# Final.net
KiCad netlist of a schematic drawn in EAGLE
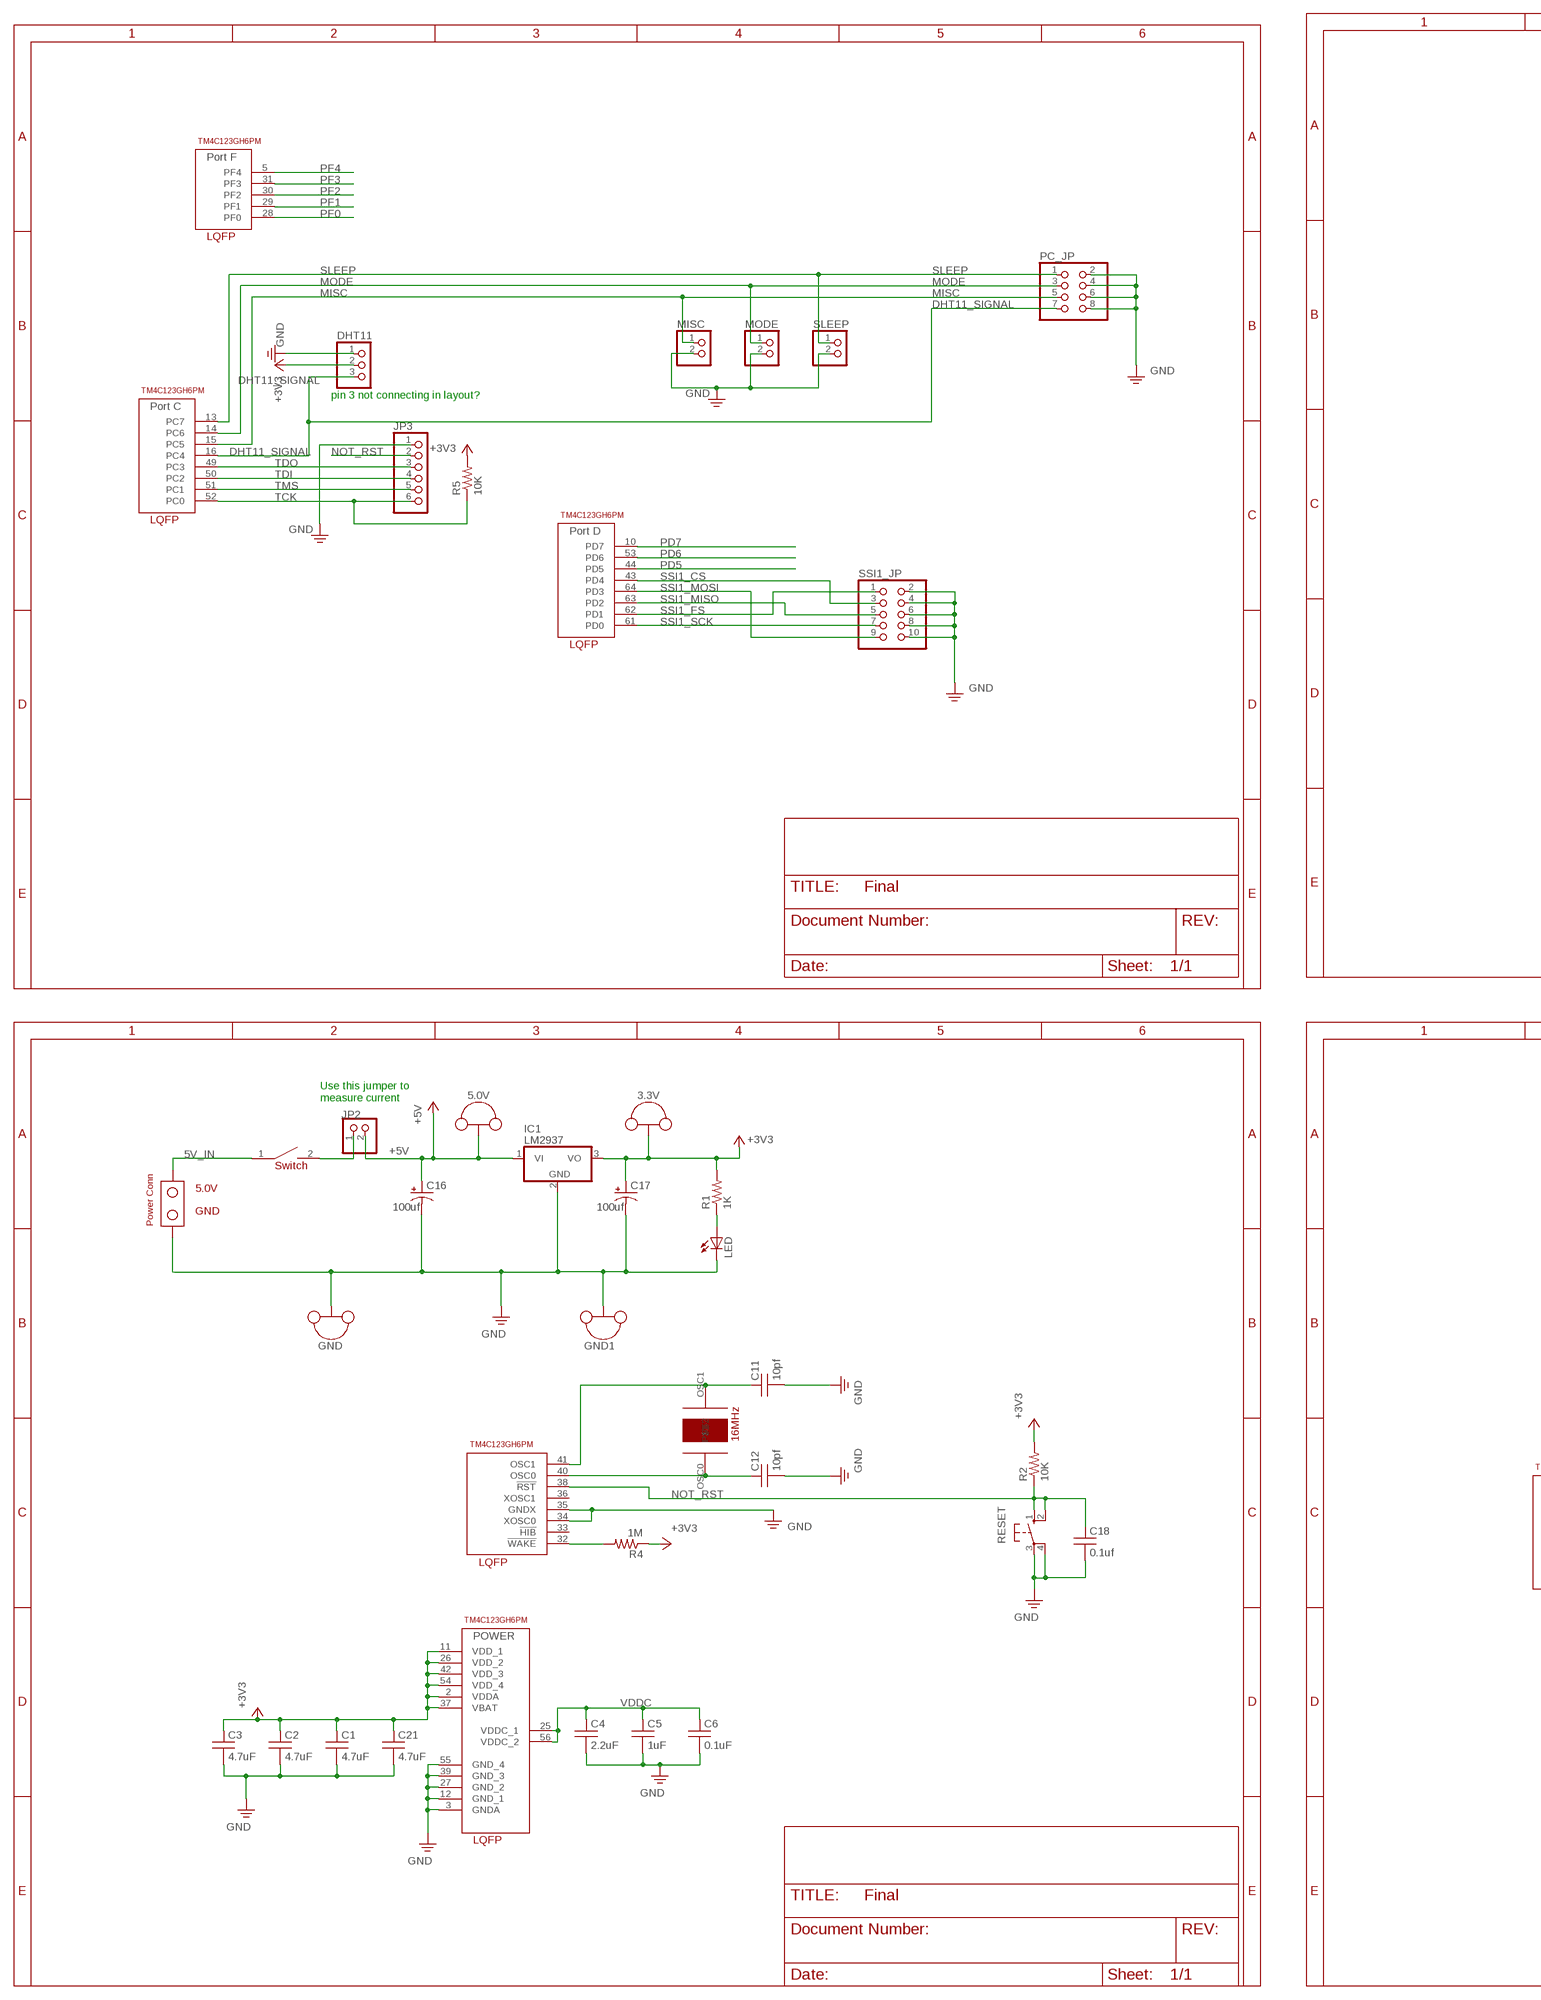
[diagram p0: schematic, sheet 1, part 1 of 2]
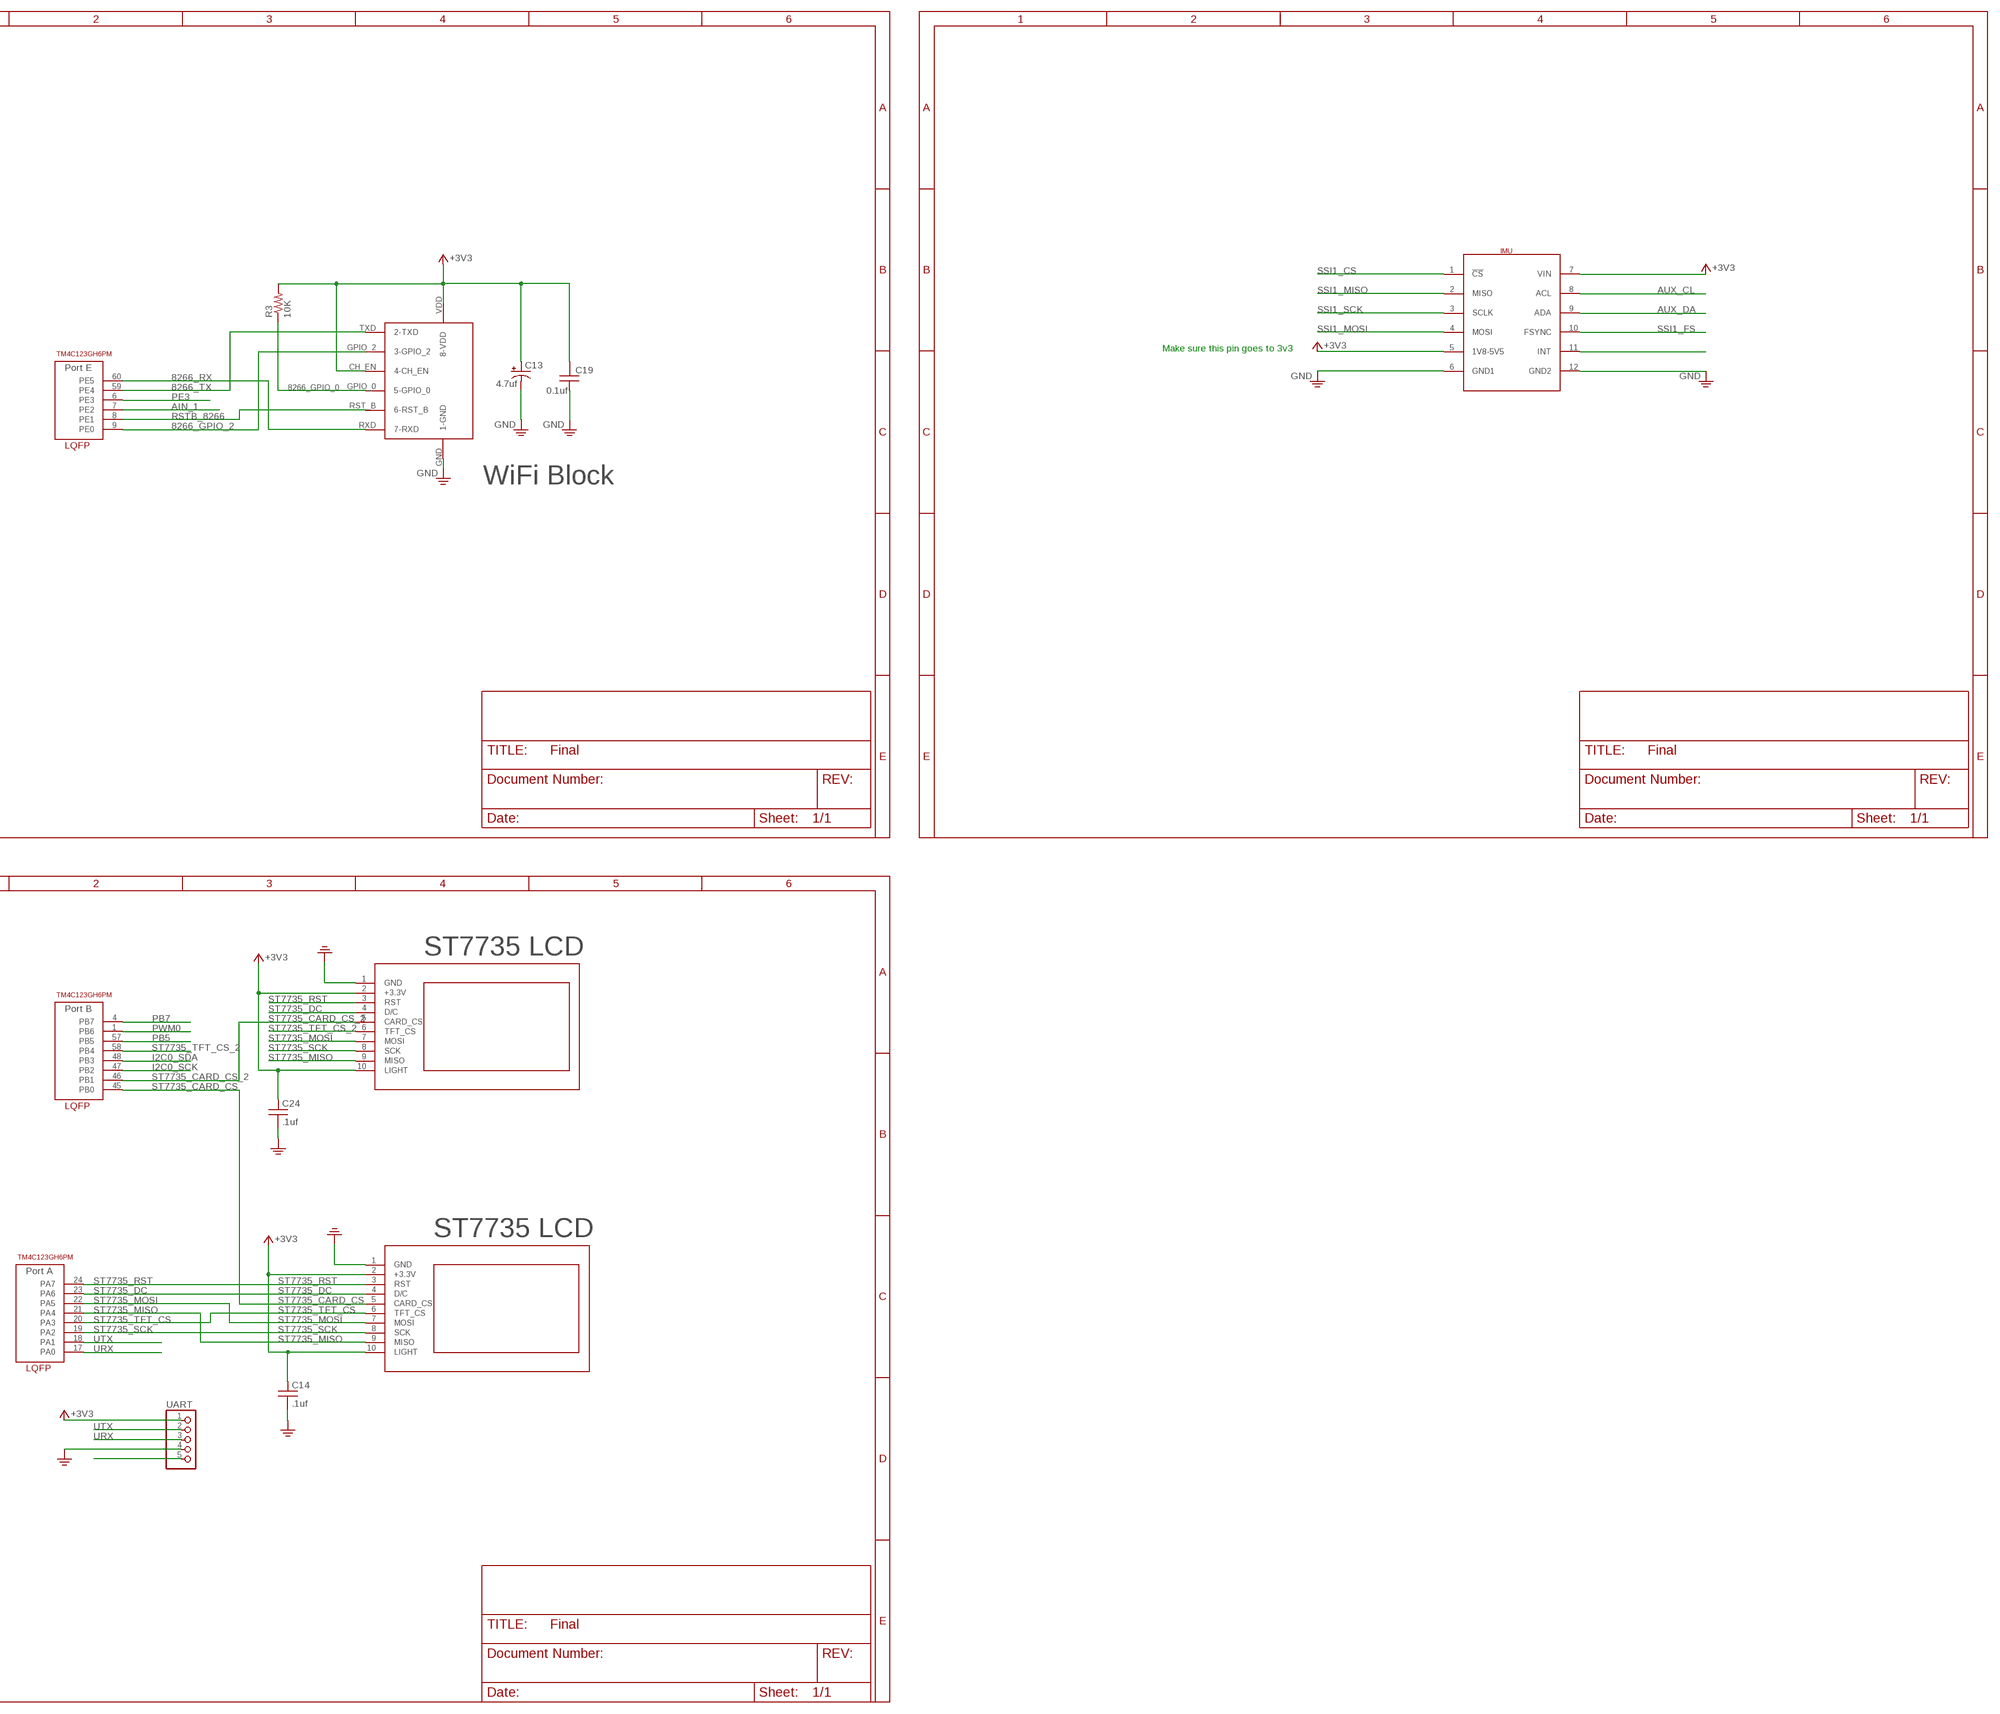
[diagram p1: schematic, sheet 1, part 2 of 2]

(export (version "E")
  (design (tool "Eeschema 10.0.6"))
  (components
    (comp (ref "3.3V")
      (value "TP_LOOP")
      (footprint "eagle-import:TP_LOOP")
      (libsource (lib "eagle-import") (part "TP_LOOP"))
    )
    (comp (ref "5.0V")
      (value "TP_LOOP")
      (footprint "eagle-import:TP_LOOP")
      (libsource (lib "eagle-import") (part "TP_LOOP"))
    )
    (comp (ref "C1")
      (value "4.7uF")
      (footprint "eagle-import:C0603K")
      (libsource (lib "eagle-import") (part "CAPACITORC0603K"))
    )
    (comp (ref "C2")
      (value "4.7uF")
      (footprint "eagle-import:C0603K")
      (libsource (lib "eagle-import") (part "CAPACITORC0603K"))
    )
    (comp (ref "C3")
      (value "4.7uF")
      (footprint "eagle-import:C0603K")
      (libsource (lib "eagle-import") (part "CAPACITORC0603K"))
    )
    (comp (ref "C4")
      (value "2.2uF")
      (footprint "eagle-import:C0603K")
      (libsource (lib "eagle-import") (part "CAPACITORC0603K"))
    )
    (comp (ref "C5")
      (value "1uF")
      (footprint "eagle-import:C0603K")
      (libsource (lib "eagle-import") (part "CAPACITORC0603K"))
    )
    (comp (ref "C6")
      (value "0.1uF")
      (footprint "eagle-import:C0603K")
      (libsource (lib "eagle-import") (part "CAPACITORC0603K"))
    )
    (comp (ref "C11")
      (value "10pf")
      (footprint "eagle-import:CAP100MIL")
      (libsource (lib "eagle-import") (part "CAPACITOR025-024X044"))
    )
    (comp (ref "C12")
      (value "10pf")
      (footprint "eagle-import:CAP100MIL")
      (libsource (lib "eagle-import") (part "CAPACITOR025-024X044"))
    )
    (comp (ref "C13")
      (value "4.7uf")
      (footprint "eagle-import:CAP200MILPOLARIZED")
      (libsource (lib "eagle-import") (part "CAPACITOR_POLARIZEDE5-6"))
    )
    (comp (ref "C14")
      (value ".1uf")
      (footprint "eagle-import:CAP200MIL")
      (libsource (lib "eagle-import") (part "CAPACITOR050-024X044"))
    )
    (comp (ref "C16")
      (value "100uf")
      (footprint "eagle-import:CAP200MILPOLARIZED")
      (libsource (lib "eagle-import") (part "CAPACITOR_POLARIZEDE5-6"))
    )
    (comp (ref "C17")
      (value "100uf")
      (footprint "eagle-import:CAP200MILPOLARIZED")
      (libsource (lib "eagle-import") (part "CAPACITOR_POLARIZEDE5-6"))
    )
    (comp (ref "C18")
      (value "0.1uf")
      (footprint "eagle-import:CAP100MIL")
      (libsource (lib "eagle-import") (part "CAPACITOR025-024X044"))
    )
    (comp (ref "C19")
      (value "0.1uf")
      (footprint "eagle-import:CAP200MIL")
      (libsource (lib "eagle-import") (part "CAPACITOR050-024X044"))
    )
    (comp (ref "C21")
      (value "4.7uF")
      (footprint "eagle-import:C0603K")
      (libsource (lib "eagle-import") (part "CAPACITORC0603K"))
    )
    (comp (ref "C24")
      (value ".1uf")
      (footprint "eagle-import:CAP200MIL")
      (libsource (lib "eagle-import") (part "CAPACITOR050-024X044"))
    )
    (comp (ref "DHT11")
      (value "PINHD-1X3")
      (footprint "eagle-import:1X03")
      (libsource (lib "eagle-import") (part "PINHD-1X3"))
    )
    (comp (ref "GND")
      (value "TP_LOOP")
      (footprint "eagle-import:TP_LOOP")
      (libsource (lib "eagle-import") (part "TP_LOOP"))
    )
    (comp (ref "GND1")
      (value "TP_LOOP")
      (footprint "eagle-import:TP_LOOP")
      (libsource (lib "eagle-import") (part "TP_LOOP"))
    )
    (comp (ref "IC1")
      (value "LM2937")
      (footprint "eagle-import:TO220")
      (libsource (lib "eagle-import") (part "LM2937"))
    )
    (comp (ref "IMU")
      (value "SEN-15335")
      (footprint "eagle-import:SEN-15335")
      (libsource (lib "eagle-import") (part "SEN-15335"))
    )
    (comp (ref "JP2")
      (value "PINHD-1X2")
      (footprint "eagle-import:1X02")
      (libsource (lib "eagle-import") (part "PINHD-1X2"))
    )
    (comp (ref "JP3")
      (value "PINHD-1X6")
      (footprint "eagle-import:1X06")
      (libsource (lib "eagle-import") (part "PINHD-1X6"))
    )
    (comp (ref "LED")
      (value "LED5MM")
      (footprint "eagle-import:LED5MM")
      (libsource (lib "eagle-import") (part "LED5MM"))
    )
    (comp (ref "MISC")
      (value "PINHD-1X2")
      (footprint "eagle-import:1X02")
      (libsource (lib "eagle-import") (part "PINHD-1X2"))
    )
    (comp (ref "MODE")
      (value "PINHD-1X2")
      (footprint "eagle-import:1X02")
      (libsource (lib "eagle-import") (part "PINHD-1X2"))
    )
    (comp (ref "PC_JP")
      (value "PINHD-2X4")
      (footprint "eagle-import:2X04")
      (libsource (lib "eagle-import") (part "PINHD-2X4"))
    )
    (comp (ref "POWER_SWITCH")
      (value "SW_POWER_100MIL")
      (footprint "eagle-import:SW_POWER")
      (libsource (lib "eagle-import") (part "SW_POWER_100MIL"))
    )
    (comp (ref "R1")
      (value "1K")
      (footprint "eagle-import:RES200MIL")
      (libsource (lib "eagle-import") (part "RESISTOR0204/5"))
    )
    (comp (ref "R2")
      (value "10K")
      (footprint "eagle-import:RES200MIL")
      (libsource (lib "eagle-import") (part "RESISTOR0204/5"))
    )
    (comp (ref "R3")
      (value "10K")
      (footprint "eagle-import:RES300MIL")
      (libsource (lib "eagle-import") (part "RESISTOR0204/7"))
    )
    (comp (ref "R4")
      (value "1M")
      (footprint "eagle-import:RES200MIL")
      (libsource (lib "eagle-import") (part "RESISTOR0204/5"))
    )
    (comp (ref "R5")
      (value "10K")
      (footprint "eagle-import:RES200MIL")
      (libsource (lib "eagle-import") (part "RESISTOR0204/5"))
    )
    (comp (ref "RESET")
      (value "B3F-1052")
      (footprint "eagle-import:B3F-10XX")
      (fields (field (name "MPN") "B3F-1000"))
      (libsource (lib "eagle-import") (part "B3F-1052"))
    )
    (comp (ref "SLEEP")
      (value "PINHD-1X2")
      (footprint "eagle-import:1X02")
      (libsource (lib "eagle-import") (part "PINHD-1X2"))
    )
    (comp (ref "SSI1_JP")
      (value "PINHD-2X5")
      (footprint "eagle-import:2X05")
      (libsource (lib "eagle-import") (part "PINHD-2X5"))
    )
    (comp (ref "U$1")
      (value "TM4C123GH6PM")
      (footprint "eagle-import:QFP50P1200X1200X160-64N")
      (libsource (lib "eagle-import") (part "TM4C123GH6PM"))
    )
    (comp (ref "U$2")
      (value "16MHZ_CRYSTAL")
      (footprint "eagle-import:16MHZ_CRYSTAL")
      (libsource (lib "eagle-import") (part "16MHZ_CRYSTAL"))
    )
    (comp (ref "U$3")
      (value "ESP_8266")
      (footprint "eagle-import:ESP8266")
      (libsource (lib "eagle-import") (part "ESP_8266"))
    )
    (comp (ref "U$4")
      (value "POWER_CONN")
      (footprint "eagle-import:POWER_CONN")
      (libsource (lib "eagle-import") (part "POWER_CONN"))
    )
    (comp (ref "U$5")
      (value "ST7735")
      (footprint "eagle-import:ST7735")
      (libsource (lib "eagle-import") (part "ST7735"))
    )
    (comp (ref "U$6")
      (value "ST7735")
      (footprint "eagle-import:ST7735")
      (libsource (lib "eagle-import") (part "ST7735"))
    )
    (comp (ref "UART")
      (value "PINHD-1X5")
      (footprint "eagle-import:1X05")
      (libsource (lib "eagle-import") (part "PINHD-1X5"))
    )
  )
  (nets
    (net (code "1") (name "+3V3") (class "Default")
      (node (ref "3.3V") (pin "P$1") (pinfunction "TP_P$1") (pintype "bidirectional"))
      (node (ref "3.3V") (pin "P$2") (pinfunction "TP_P$2") (pintype "bidirectional"))
      (node (ref "C1") (pin "1") (pinfunction "1_1") (pintype "passive"))
      (node (ref "C13") (pin "+") (pinfunction "+_+") (pintype "passive"))
      (node (ref "C14") (pin "1") (pinfunction "1_1") (pintype "passive"))
      (node (ref "C17") (pin "+") (pinfunction "+_+") (pintype "passive"))
      (node (ref "C19") (pin "2") (pinfunction "2_2") (pintype "passive"))
      (node (ref "C2") (pin "1") (pinfunction "1_1") (pintype "passive"))
      (node (ref "C21") (pin "1") (pinfunction "1_1") (pintype "passive"))
      (node (ref "C24") (pin "1") (pinfunction "1_1") (pintype "passive"))
      (node (ref "C3") (pin "1") (pinfunction "1_1") (pintype "passive"))
      (node (ref "DHT11") (pin "2") (pinfunction "2_2") (pintype "passive"))
      (node (ref "IC1") (pin "3") (pinfunction "VO_3") (pintype "passive"))
      (node (ref "IMU") (pin "5") (pinfunction "1V8-5V5_5") (pintype "bidirectional"))
      (node (ref "IMU") (pin "7") (pinfunction "VIN_7") (pintype "bidirectional"))
      (node (ref "R1") (pin "2") (pinfunction "2_2") (pintype "passive"))
      (node (ref "R2") (pin "2") (pinfunction "2_2") (pintype "passive"))
      (node (ref "R3") (pin "2") (pinfunction "2_2") (pintype "passive"))
      (node (ref "R4") (pin "1") (pinfunction "1_1") (pintype "passive"))
      (node (ref "R5") (pin "2") (pinfunction "2_2") (pintype "passive"))
      (node (ref "U$1") (pin "11") (pinfunction "VDD_1_11") (pintype "bidirectional"))
      (node (ref "U$1") (pin "2") (pinfunction "VDDA_2") (pintype "bidirectional"))
      (node (ref "U$1") (pin "26") (pinfunction "VDD_2_26") (pintype "bidirectional"))
      (node (ref "U$1") (pin "37") (pinfunction "VBAT_37") (pintype "bidirectional"))
      (node (ref "U$1") (pin "42") (pinfunction "VDD_3_42") (pintype "bidirectional"))
      (node (ref "U$1") (pin "54") (pinfunction "VDD_4_54") (pintype "bidirectional"))
      (node (ref "U$3") (pin "CH_EN") (pinfunction "4-CH_EN_CH_EN") (pintype "bidirectional"))
      (node (ref "U$3") (pin "VDD") (pinfunction "8-VDD_VDD") (pintype "bidirectional"))
      (node (ref "U$5") (pin "10") (pinfunction "LIGHT_10") (pintype "bidirectional"))
      (node (ref "U$5") (pin "2") (pinfunction "+3.3V_2") (pintype "bidirectional"))
      (node (ref "U$6") (pin "10") (pinfunction "LIGHT_10") (pintype "bidirectional"))
      (node (ref "U$6") (pin "2") (pinfunction "+3.3V_2") (pintype "bidirectional"))
      (node (ref "UART") (pin "1") (pinfunction "1_1") (pintype "passive"))
    )
    (net (code "2") (name "+5V") (class "Default")
      (node (ref "5.0V") (pin "P$1") (pinfunction "TP_P$1") (pintype "bidirectional"))
      (node (ref "5.0V") (pin "P$2") (pinfunction "TP_P$2") (pintype "bidirectional"))
      (node (ref "C16") (pin "+") (pinfunction "+_+") (pintype "passive"))
      (node (ref "IC1") (pin "1") (pinfunction "VI_1") (pintype "input"))
      (node (ref "JP2") (pin "2") (pinfunction "2_2") (pintype "passive"))
    )
    (net (code "3") (name "/5V_IN") (class "Default")
      (node (ref "POWER_SWITCH") (pin "1") (pinfunction "P$1_1") (pintype "bidirectional"))
      (node (ref "U$4") (pin "VDD") (pinfunction "VDD_VDD") (pintype "bidirectional"))
    )
    (net (code "4") (name "/8266_GPIO_0") (class "Default")
      (node (ref "R3") (pin "1") (pinfunction "1_1") (pintype "passive"))
      (node (ref "U$3") (pin "GPIO_0") (pinfunction "5-GPIO_0_GPIO_0") (pintype "bidirectional"))
    )
    (net (code "5") (name "/8266_GPIO_2") (class "Default")
      (node (ref "U$1") (pin "9") (pinfunction "PE0_9") (pintype "bidirectional"))
      (node (ref "U$3") (pin "GPIO_2") (pinfunction "3-GPIO_2_GPIO_2") (pintype "bidirectional"))
    )
    (net (code "6") (name "/8266_RX") (class "Default")
      (node (ref "U$1") (pin "60") (pinfunction "PE5_60") (pintype "bidirectional"))
      (node (ref "U$3") (pin "RXD") (pinfunction "7-RXD_RXD") (pintype "bidirectional"))
    )
    (net (code "7") (name "/8266_TX") (class "Default")
      (node (ref "U$1") (pin "59") (pinfunction "PE4_59") (pintype "bidirectional"))
      (node (ref "U$3") (pin "TXD") (pinfunction "2-TXD_TXD") (pintype "bidirectional"))
    )
    (net (code "8") (name "/AIN_1") (class "Default")
      (node (ref "U$1") (pin "7") (pinfunction "PE2_7") (pintype "bidirectional"))
    )
    (net (code "9") (name "/AUX_CL") (class "Default")
      (node (ref "IMU") (pin "8") (pinfunction "ACL_8") (pintype "bidirectional"))
    )
    (net (code "10") (name "/AUX_DA") (class "Default")
      (node (ref "IMU") (pin "9") (pinfunction "ADA_9") (pintype "bidirectional"))
    )
    (net (code "11") (name "/DHT11_SIGNAL") (class "Default")
      (node (ref "DHT11") (pin "3") (pinfunction "3_3") (pintype "passive"))
      (node (ref "PC_JP") (pin "7") (pinfunction "7_7") (pintype "passive"))
      (node (ref "U$1") (pin "16") (pinfunction "PC4_16") (pintype "bidirectional"))
    )
    (net (code "12") (name "/I2C0_SCK") (class "Default")
      (node (ref "U$1") (pin "47") (pinfunction "PB2_47") (pintype "bidirectional"))
    )
    (net (code "13") (name "/I2C0_SDA") (class "Default")
      (node (ref "U$1") (pin "48") (pinfunction "PB3_48") (pintype "bidirectional"))
    )
    (net (code "14") (name "/MISC") (class "Default")
      (node (ref "MISC") (pin "1") (pinfunction "1_1") (pintype "passive"))
      (node (ref "PC_JP") (pin "5") (pinfunction "5_5") (pintype "passive"))
      (node (ref "U$1") (pin "15") (pinfunction "PC5_15") (pintype "bidirectional"))
    )
    (net (code "15") (name "/MODE") (class "Default")
      (node (ref "MODE") (pin "1") (pinfunction "1_1") (pintype "passive"))
      (node (ref "PC_JP") (pin "3") (pinfunction "3_3") (pintype "passive"))
      (node (ref "U$1") (pin "14") (pinfunction "PC6_14") (pintype "bidirectional"))
    )
    (net (code "16") (name "/NOT_RST") (class "Default")
      (node (ref "C18") (pin "1") (pinfunction "1_1") (pintype "passive"))
      (node (ref "JP3") (pin "2") (pinfunction "2_2") (pintype "passive"))
      (node (ref "R2") (pin "1") (pinfunction "1_1") (pintype "passive"))
      (node (ref "RESET") (pin "1") (pinfunction "S_1") (pintype "passive"))
      (node (ref "RESET") (pin "2") (pinfunction "S1_2") (pintype "passive"))
      (node (ref "U$1") (pin "38") (pinfunction "~{RST}_38") (pintype "bidirectional"))
    )
    (net (code "17") (name "/PB5") (class "Default")
      (node (ref "U$1") (pin "57") (pinfunction "PB5_57") (pintype "bidirectional"))
    )
    (net (code "18") (name "/PB7") (class "Default")
      (node (ref "U$1") (pin "4") (pinfunction "PB7_4") (pintype "bidirectional"))
    )
    (net (code "19") (name "/PD5") (class "Default")
      (node (ref "U$1") (pin "44") (pinfunction "PD5_44") (pintype "bidirectional"))
    )
    (net (code "20") (name "/PD6") (class "Default")
      (node (ref "U$1") (pin "53") (pinfunction "PD6_53") (pintype "bidirectional"))
    )
    (net (code "21") (name "/PD7") (class "Default")
      (node (ref "U$1") (pin "10") (pinfunction "PD7_10") (pintype "bidirectional"))
    )
    (net (code "22") (name "/PE3") (class "Default")
      (node (ref "U$1") (pin "6") (pinfunction "PE3_6") (pintype "bidirectional"))
    )
    (net (code "23") (name "/PF0") (class "Default")
      (node (ref "U$1") (pin "28") (pinfunction "PF0_28") (pintype "bidirectional"))
    )
    (net (code "24") (name "/PF1") (class "Default")
      (node (ref "U$1") (pin "29") (pinfunction "PF1_29") (pintype "bidirectional"))
    )
    (net (code "25") (name "/PF2") (class "Default")
      (node (ref "U$1") (pin "30") (pinfunction "PF2_30") (pintype "bidirectional"))
    )
    (net (code "26") (name "/PF3") (class "Default")
      (node (ref "U$1") (pin "31") (pinfunction "PF3_31") (pintype "bidirectional"))
    )
    (net (code "27") (name "/PF4") (class "Default")
      (node (ref "U$1") (pin "5") (pinfunction "PF4_5") (pintype "bidirectional"))
    )
    (net (code "28") (name "/PWM0") (class "Default")
      (node (ref "U$1") (pin "1") (pinfunction "PB6_1") (pintype "bidirectional"))
    )
    (net (code "29") (name "/RSTB_8266") (class "Default")
      (node (ref "U$1") (pin "8") (pinfunction "PE1_8") (pintype "bidirectional"))
      (node (ref "U$3") (pin "RST_B") (pinfunction "6-RST_B_RST_B") (pintype "bidirectional"))
    )
    (net (code "30") (name "/SLEEP") (class "Default")
      (node (ref "PC_JP") (pin "1") (pinfunction "1_1") (pintype "passive"))
      (node (ref "SLEEP") (pin "1") (pinfunction "1_1") (pintype "passive"))
      (node (ref "U$1") (pin "13") (pinfunction "PC7_13") (pintype "bidirectional"))
    )
    (net (code "31") (name "/SSI1_CS") (class "Default")
      (node (ref "IMU") (pin "1") (pinfunction "~{CS}_1") (pintype "bidirectional"))
      (node (ref "SSI1_JP") (pin "3") (pinfunction "3_3") (pintype "passive"))
      (node (ref "U$1") (pin "43") (pinfunction "PD4_43") (pintype "bidirectional"))
    )
    (net (code "32") (name "/SSI1_FS") (class "Default")
      (node (ref "IMU") (pin "10") (pinfunction "FSYNC_10") (pintype "bidirectional"))
      (node (ref "SSI1_JP") (pin "1") (pinfunction "1_1") (pintype "passive"))
      (node (ref "U$1") (pin "62") (pinfunction "PD1_62") (pintype "bidirectional"))
    )
    (net (code "33") (name "/SSI1_MISO") (class "Default")
      (node (ref "IMU") (pin "2") (pinfunction "MISO_2") (pintype "bidirectional"))
      (node (ref "SSI1_JP") (pin "5") (pinfunction "5_5") (pintype "passive"))
      (node (ref "U$1") (pin "63") (pinfunction "PD2_63") (pintype "bidirectional"))
    )
    (net (code "34") (name "/SSI1_MOSI") (class "Default")
      (node (ref "IMU") (pin "4") (pinfunction "MOSI_4") (pintype "bidirectional"))
      (node (ref "SSI1_JP") (pin "9") (pinfunction "9_9") (pintype "passive"))
      (node (ref "U$1") (pin "64") (pinfunction "PD3_64") (pintype "bidirectional"))
    )
    (net (code "35") (name "/SSI1_SCK") (class "Default")
      (node (ref "IMU") (pin "3") (pinfunction "SCLK_3") (pintype "bidirectional"))
      (node (ref "SSI1_JP") (pin "7") (pinfunction "7_7") (pintype "passive"))
      (node (ref "U$1") (pin "61") (pinfunction "PD0_61") (pintype "bidirectional"))
    )
    (net (code "36") (name "/ST7735_CARD_CS") (class "Default")
      (node (ref "U$1") (pin "45") (pinfunction "PB0_45") (pintype "bidirectional"))
      (node (ref "U$5") (pin "5") (pinfunction "CARD_CS_5") (pintype "bidirectional"))
    )
    (net (code "37") (name "/ST7735_CARD_CS_2") (class "Default")
      (node (ref "U$1") (pin "46") (pinfunction "PB1_46") (pintype "bidirectional"))
      (node (ref "U$6") (pin "5") (pinfunction "CARD_CS_5") (pintype "bidirectional"))
    )
    (net (code "38") (name "/ST7735_DC") (class "Default")
      (node (ref "U$1") (pin "23") (pinfunction "PA6_23") (pintype "bidirectional"))
      (node (ref "U$5") (pin "4") (pinfunction "D/C_4") (pintype "bidirectional"))
      (node (ref "U$6") (pin "4") (pinfunction "D/C_4") (pintype "bidirectional"))
    )
    (net (code "39") (name "/ST7735_MISO") (class "Default")
      (node (ref "U$1") (pin "21") (pinfunction "PA4_21") (pintype "bidirectional"))
      (node (ref "U$5") (pin "9") (pinfunction "MISO_9") (pintype "bidirectional"))
      (node (ref "U$6") (pin "9") (pinfunction "MISO_9") (pintype "bidirectional"))
    )
    (net (code "40") (name "/ST7735_MOSI") (class "Default")
      (node (ref "U$1") (pin "22") (pinfunction "PA5_22") (pintype "bidirectional"))
      (node (ref "U$5") (pin "7") (pinfunction "MOSI_7") (pintype "bidirectional"))
      (node (ref "U$6") (pin "7") (pinfunction "MOSI_7") (pintype "bidirectional"))
    )
    (net (code "41") (name "/ST7735_RST") (class "Default")
      (node (ref "U$1") (pin "24") (pinfunction "PA7_24") (pintype "bidirectional"))
      (node (ref "U$5") (pin "3") (pinfunction "RST_3") (pintype "bidirectional"))
      (node (ref "U$6") (pin "3") (pinfunction "RST_3") (pintype "bidirectional"))
    )
    (net (code "42") (name "/ST7735_SCK") (class "Default")
      (node (ref "U$1") (pin "19") (pinfunction "PA2_19") (pintype "bidirectional"))
      (node (ref "U$5") (pin "8") (pinfunction "SCK_8") (pintype "bidirectional"))
      (node (ref "U$6") (pin "8") (pinfunction "SCK_8") (pintype "bidirectional"))
    )
    (net (code "43") (name "/ST7735_TFT_CS") (class "Default")
      (node (ref "U$1") (pin "20") (pinfunction "PA3_20") (pintype "bidirectional"))
      (node (ref "U$5") (pin "6") (pinfunction "TFT_CS_6") (pintype "bidirectional"))
    )
    (net (code "44") (name "/ST7735_TFT_CS_2") (class "Default")
      (node (ref "U$1") (pin "58") (pinfunction "PB4_58") (pintype "bidirectional"))
      (node (ref "U$6") (pin "6") (pinfunction "TFT_CS_6") (pintype "bidirectional"))
    )
    (net (code "45") (name "/TCK") (class "Default")
      (node (ref "JP3") (pin "6") (pinfunction "6_6") (pintype "passive"))
      (node (ref "R5") (pin "1") (pinfunction "1_1") (pintype "passive"))
      (node (ref "U$1") (pin "52") (pinfunction "PC0_52") (pintype "bidirectional"))
    )
    (net (code "46") (name "/TDI") (class "Default")
      (node (ref "JP3") (pin "4") (pinfunction "4_4") (pintype "passive"))
      (node (ref "U$1") (pin "50") (pinfunction "PC2_50") (pintype "bidirectional"))
    )
    (net (code "47") (name "/TDO") (class "Default")
      (node (ref "JP3") (pin "3") (pinfunction "3_3") (pintype "passive"))
      (node (ref "U$1") (pin "49") (pinfunction "PC3_49") (pintype "bidirectional"))
    )
    (net (code "48") (name "/TMS") (class "Default")
      (node (ref "JP3") (pin "5") (pinfunction "5_5") (pintype "passive"))
      (node (ref "U$1") (pin "51") (pinfunction "PC1_51") (pintype "bidirectional"))
    )
    (net (code "49") (name "/URX") (class "Default")
      (node (ref "U$1") (pin "17") (pinfunction "PA0_17") (pintype "bidirectional"))
      (node (ref "UART") (pin "3") (pinfunction "3_3") (pintype "passive"))
    )
    (net (code "50") (name "/UTX") (class "Default")
      (node (ref "U$1") (pin "18") (pinfunction "PA1_18") (pintype "bidirectional"))
      (node (ref "UART") (pin "2") (pinfunction "2_2") (pintype "passive"))
    )
    (net (code "51") (name "/VDDC") (class "Default")
      (node (ref "C4") (pin "1") (pinfunction "1_1") (pintype "passive"))
      (node (ref "C5") (pin "1") (pinfunction "1_1") (pintype "passive"))
      (node (ref "C6") (pin "1") (pinfunction "1_1") (pintype "passive"))
      (node (ref "U$1") (pin "25") (pinfunction "VDDC_1_25") (pintype "bidirectional"))
      (node (ref "U$1") (pin "56") (pinfunction "VDDC_2_56") (pintype "bidirectional"))
    )
    (net (code "52") (name "GND") (class "Default")
      (node (ref "C1") (pin "2") (pinfunction "2_2") (pintype "passive"))
      (node (ref "C11") (pin "2") (pinfunction "2_2") (pintype "passive"))
      (node (ref "C12") (pin "2") (pinfunction "2_2") (pintype "passive"))
      (node (ref "C13") (pin "-") (pinfunction "-_-") (pintype "passive"))
      (node (ref "C14") (pin "2") (pinfunction "2_2") (pintype "passive"))
      (node (ref "C16") (pin "-") (pinfunction "-_-") (pintype "passive"))
      (node (ref "C17") (pin "-") (pinfunction "-_-") (pintype "passive"))
      (node (ref "C18") (pin "2") (pinfunction "2_2") (pintype "passive"))
      (node (ref "C19") (pin "1") (pinfunction "1_1") (pintype "passive"))
      (node (ref "C2") (pin "2") (pinfunction "2_2") (pintype "passive"))
      (node (ref "C21") (pin "2") (pinfunction "2_2") (pintype "passive"))
      (node (ref "C24") (pin "2") (pinfunction "2_2") (pintype "passive"))
      (node (ref "C3") (pin "2") (pinfunction "2_2") (pintype "passive"))
      (node (ref "C4") (pin "2") (pinfunction "2_2") (pintype "passive"))
      (node (ref "C5") (pin "2") (pinfunction "2_2") (pintype "passive"))
      (node (ref "C6") (pin "2") (pinfunction "2_2") (pintype "passive"))
      (node (ref "DHT11") (pin "1") (pinfunction "1_1") (pintype "passive"))
      (node (ref "GND") (pin "P$1") (pinfunction "TP_P$1") (pintype "bidirectional"))
      (node (ref "GND") (pin "P$2") (pinfunction "TP_P$2") (pintype "bidirectional"))
      (node (ref "GND1") (pin "P$1") (pinfunction "TP_P$1") (pintype "bidirectional"))
      (node (ref "GND1") (pin "P$2") (pinfunction "TP_P$2") (pintype "bidirectional"))
      (node (ref "IC1") (pin "2") (pinfunction "GND_2") (pintype "passive"))
      (node (ref "IMU") (pin "12") (pinfunction "GND2_12") (pintype "bidirectional"))
      (node (ref "IMU") (pin "6") (pinfunction "GND1_6") (pintype "bidirectional"))
      (node (ref "JP3") (pin "1") (pinfunction "1_1") (pintype "passive"))
      (node (ref "LED") (pin "K") (pinfunction "C_K") (pintype "passive"))
      (node (ref "MISC") (pin "2") (pinfunction "2_2") (pintype "passive"))
      (node (ref "MODE") (pin "2") (pinfunction "2_2") (pintype "passive"))
      (node (ref "PC_JP") (pin "2") (pinfunction "2_2") (pintype "passive"))
      (node (ref "PC_JP") (pin "4") (pinfunction "4_4") (pintype "passive"))
      (node (ref "PC_JP") (pin "6") (pinfunction "6_6") (pintype "passive"))
      (node (ref "PC_JP") (pin "8") (pinfunction "8_8") (pintype "passive"))
      (node (ref "RESET") (pin "3") (pinfunction "P_3") (pintype "passive"))
      (node (ref "RESET") (pin "4") (pinfunction "P1_4") (pintype "passive"))
      (node (ref "SLEEP") (pin "2") (pinfunction "2_2") (pintype "passive"))
      (node (ref "SSI1_JP") (pin "10") (pinfunction "10_10") (pintype "passive"))
      (node (ref "SSI1_JP") (pin "2") (pinfunction "2_2") (pintype "passive"))
      (node (ref "SSI1_JP") (pin "4") (pinfunction "4_4") (pintype "passive"))
      (node (ref "SSI1_JP") (pin "6") (pinfunction "6_6") (pintype "passive"))
      (node (ref "SSI1_JP") (pin "8") (pinfunction "8_8") (pintype "passive"))
      (node (ref "U$1") (pin "12") (pinfunction "GND_1_12") (pintype "bidirectional"))
      (node (ref "U$1") (pin "27") (pinfunction "GND_2_27") (pintype "bidirectional"))
      (node (ref "U$1") (pin "3") (pinfunction "GNDA_3") (pintype "bidirectional"))
      (node (ref "U$1") (pin "34") (pinfunction "XOSC0_34") (pintype "bidirectional"))
      (node (ref "U$1") (pin "35") (pinfunction "GNDX_35") (pintype "bidirectional"))
      (node (ref "U$1") (pin "39") (pinfunction "GND_3_39") (pintype "bidirectional"))
      (node (ref "U$1") (pin "55") (pinfunction "GND_4_55") (pintype "bidirectional"))
      (node (ref "U$3") (pin "GND") (pinfunction "1-GND_GND") (pintype "bidirectional"))
      (node (ref "U$4") (pin "GND") (pinfunction "GND_GND") (pintype "bidirectional"))
      (node (ref "U$5") (pin "1") (pinfunction "GND_1") (pintype "bidirectional"))
      (node (ref "U$6") (pin "1") (pinfunction "GND_1") (pintype "bidirectional"))
      (node (ref "UART") (pin "4") (pinfunction "4_4") (pintype "passive"))
    )
    (net (code "53") (name "Net-(LED-PadA)") (class "Default")
      (node (ref "LED") (pin "A") (pinfunction "A_A") (pintype "passive"))
      (node (ref "R1") (pin "1") (pinfunction "1_1") (pintype "passive"))
    )
    (net (code "54") (name "Net-(POWER_SWITCH-P$2)") (class "Default")
      (node (ref "JP2") (pin "1") (pinfunction "1_1") (pintype "passive"))
      (node (ref "POWER_SWITCH") (pin "2") (pinfunction "P$2_2") (pintype "bidirectional"))
    )
    (net (code "55") (name "Net-(U$1G-OSC0)") (class "Default")
      (node (ref "C12") (pin "1") (pinfunction "1_1") (pintype "passive"))
      (node (ref "U$1") (pin "40") (pinfunction "OSC0_40") (pintype "bidirectional"))
      (node (ref "U$2") (pin "OSC0") (pinfunction "P$1_OSC0") (pintype "bidirectional"))
    )
    (net (code "56") (name "Net-(U$1G-OSC1)") (class "Default")
      (node (ref "C11") (pin "1") (pinfunction "1_1") (pintype "passive"))
      (node (ref "U$1") (pin "41") (pinfunction "OSC1_41") (pintype "bidirectional"))
      (node (ref "U$2") (pin "OSC1") (pinfunction "P$2_OSC1") (pintype "bidirectional"))
    )
    (net (code "57") (name "Net-(U$1G-~{WAKE})") (class "Default")
      (node (ref "R4") (pin "2") (pinfunction "2_2") (pintype "passive"))
      (node (ref "U$1") (pin "32") (pinfunction "~{WAKE}_32") (pintype "bidirectional"))
    )
    (net (code "58") (name "unconnected-(IMU-INT-Pad11)") (class "Default")
      (node (ref "IMU") (pin "11") (pinfunction "INT_11") (pintype "bidirectional"))
    )
    (net (code "59") (name "unconnected-(U$1G-XOSC1-Pad36)") (class "Default")
      (node (ref "U$1") (pin "36") (pinfunction "XOSC1_36") (pintype "bidirectional"))
    )
    (net (code "60") (name "unconnected-(U$1G-~{HIB}-Pad33)") (class "Default")
      (node (ref "U$1") (pin "33") (pinfunction "~{HIB}_33") (pintype "bidirectional"))
    )
    (net (code "61") (name "unconnected-(UART-Pad5)") (class "Default")
      (node (ref "UART") (pin "5") (pinfunction "5_5") (pintype "passive"))
    )
  )
)
